# CPU.net
KiCad netlist of a schematic drawn in Altium Designer
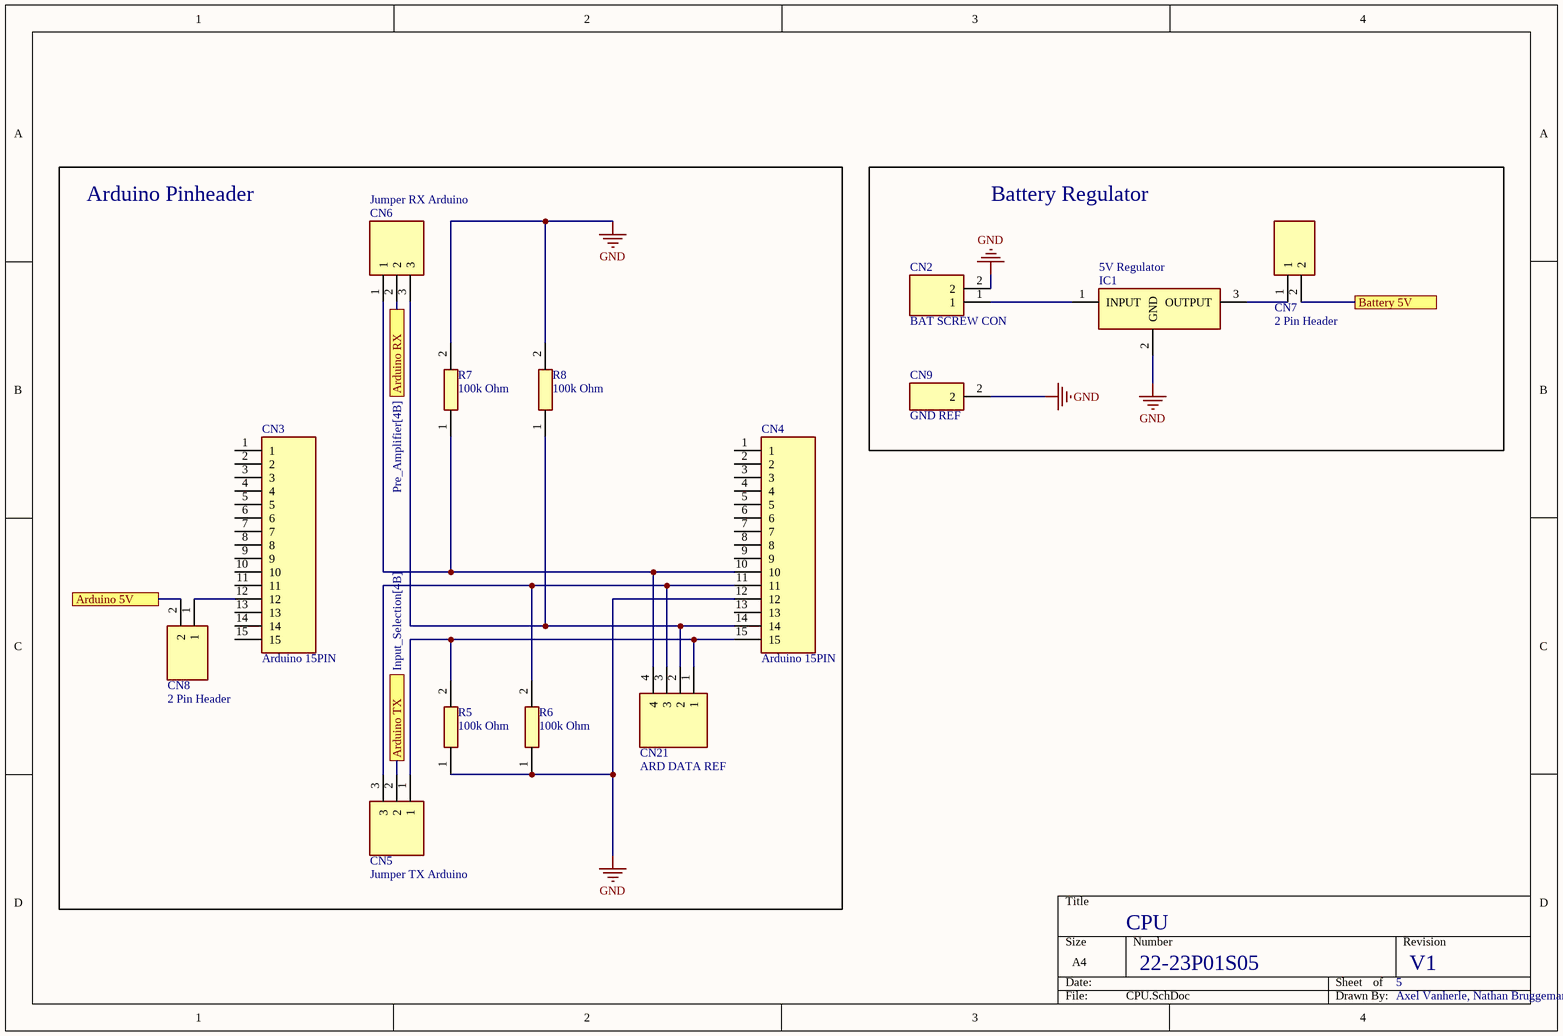
[diagram p0: CPU.SchDoc]

(export (version "E")
  (design (tool "Eeschema 10.0.6"))
  (components
    (comp (ref "CN2")
      (value "BAT SCREW CON")
      (footprint "BAT SCREW CON")
      (description "Connector")
      (fields
        (field (name "MANUFACTURER_PART_NUMBER") "TB006-508-02BE")
        (field (name "MOUSER PART NUMBER") "490-TB006-508-02BE")
      )
      (libsource (lib "IR_Communication_Schematic_Lib") (part "BAT SCREW CON"))
    )
    (comp (ref "CN3")
      (value "Arduino 15PIN")
      (footprint "15 Pin Header")
      (description "15 Pin Header Connector")
      (fields
        (field (name "MANUFACTURER_PART_NUMBER") "PRT-16279")
        (field (name "MOUSER PART NUMBER") "474-PRT-16279")
      )
      (libsource (lib "IR_Communication_Schematic_Lib") (part "15 Pin Header"))
    )
    (comp (ref "CN4")
      (value "Arduino 15PIN")
      (footprint "15 Pin Header")
      (description "15 Pin Header Connector")
      (fields
        (field (name "MANUFACTURER_PART_NUMBER") "PRT-16279")
        (field (name "MOUSER PART NUMBER") "474-PRT-16279")
      )
      (libsource (lib "IR_Communication_Schematic_Lib") (part "15 Pin Header"))
    )
    (comp (ref "CN5")
      (value "Jumper TX Arduino")
      (footprint "3 Pin Header")
      (description "TSW-103-07-G-S")
      (fields (field (name "MOUSER PART NUMBER") "200-TSW10307GS"))
      (libsource (lib "IR_Communication_Schematic_Lib") (part "3 Pin Header"))
    )
    (comp (ref "CN6")
      (value "Jumper RX Arduino")
      (footprint "3 Pin Header")
      (description "TSW-103-07-G-S")
      (fields (field (name "MOUSER PART NUMBER") "200-TSW10307GS"))
      (libsource (lib "") (part "3 Pin Header_1"))
    )
    (comp (ref "CN7")
      (value "2 Pin Header")
      (footprint "2 Pin Header")
      (description "Connector")
      (fields
        (field (name "MANUFACTURER_PART_NUMBER") "5-146284-2")
        (field (name "MOUSER PART NUMBER") "571-5-146284-2")
      )
      (libsource (lib "IR_Communication_Schematic_Lib") (part "2 Pin Header"))
    )
    (comp (ref "CN8")
      (value "2 Pin Header")
      (footprint "2 Pin Header")
      (description "Connector")
      (fields
        (field (name "MANUFACTURER_PART_NUMBER") "5-146284-2")
        (field (name "MOUSER PART NUMBER") "571-5-146284-2")
      )
      (libsource (lib "") (part "2 Pin Header_1"))
    )
    (comp (ref "CN9")
      (value "GND REF")
      (footprint "1 PIN HEADER")
      (description "Connector")
      (fields
        (field (name "MANUFACTURER_PART_NUMBER") "5-146281-1")
        (field (name "MOUSER PART NUMBER") "571-5-146281-1")
      )
      (libsource (lib "IR_Communication_Schematic_Lib") (part "1 Pin Header"))
    )
    (comp (ref "CN21")
      (value "ARD DATA REF")
      (footprint "4 PIN HEADER")
      (description "G800LW304032EU")
      (fields (field (name "MOUSER PART NUMBER") "523-G800LW304032EU"))
      (libsource (lib "IR_Communication_Schematic_Lib") (part "4 Pin Header"))
    )
    (comp (ref "IC1")
      (value "5V Regulator")
      (footprint "5V Regulator")
      (description "MC7805BDTG")
      (fields (field (name "MOUSER PART NUMBER") "863-MC7805BDTG"))
      (libsource (lib "IR_Communication_Schematic_Lib") (part "5V Regulator"))
    )
    (comp (ref "R5")
      (value "100k Ohm")
      (footprint "0805")
      (description "Resistor")
      (fields
        (field (name "MANUFACTURER_PART_NUMBER") "RP0805BRD071KL")
        (field (name "MOUSER PART NUMBER") "603-RP0805BRD071KL")
      )
      (libsource (lib "IR_Communication_Schematic_Lib") (part "Resistor"))
    )
    (comp (ref "R6")
      (value "100k Ohm")
      (footprint "0805")
      (description "Resistor")
      (fields
        (field (name "MANUFACTURER_PART_NUMBER") "RP0805BRD071KL")
        (field (name "MOUSER PART NUMBER") "603-RP0805BRD071KL")
      )
      (libsource (lib "IR_Communication_Schematic_Lib") (part "Resistor"))
    )
    (comp (ref "R7")
      (value "100k Ohm")
      (footprint "0805")
      (description "Resistor")
      (fields
        (field (name "MANUFACTURER_PART_NUMBER") "RP0805BRD071KL")
        (field (name "MOUSER PART NUMBER") "603-RP0805BRD071KL")
      )
      (libsource (lib "IR_Communication_Schematic_Lib") (part "Resistor"))
    )
    (comp (ref "R8")
      (value "100k Ohm")
      (footprint "0805")
      (description "Resistor")
      (fields
        (field (name "MANUFACTURER_PART_NUMBER") "RP0805BRD071KL")
        (field (name "MOUSER PART NUMBER") "603-RP0805BRD071KL")
      )
      (libsource (lib "IR_Communication_Schematic_Lib") (part "Resistor"))
    )
  )
  (nets
    (net (code "1") (name "/Arduino 5V") (class "Default")
      (node (ref "CN8") (pin "2") (pinfunction "2_2") (pintype "passive"))
    )
    (net (code "2") (name "/Arduino RX") (class "Default")
      (node (ref "CN6") (pin "2") (pinfunction "2_2") (pintype "passive"))
    )
    (net (code "3") (name "/Arduino TX") (class "Default")
      (node (ref "CN5") (pin "2") (pinfunction "2_2") (pintype "passive"))
    )
    (net (code "4") (name "/Battery 5V") (class "Default")
      (node (ref "CN7") (pin "2") (pinfunction "2_2") (pintype "passive"))
    )
    (net (code "5") (name "GND") (class "Default")
      (node (ref "CN2") (pin "2") (pinfunction "2_2") (pintype "passive"))
      (node (ref "CN4") (pin "12") (pinfunction "12_12") (pintype "passive"))
      (node (ref "CN9") (pin "2") (pinfunction "2_2") (pintype "passive"))
      (node (ref "IC1") (pin "2") (pinfunction "GND_2") (pintype "passive"))
      (node (ref "R5") (pin "1") (pinfunction "1_1") (pintype "passive"))
      (node (ref "R6") (pin "1") (pinfunction "1_1") (pintype "passive"))
      (node (ref "R7") (pin "2") (pinfunction "2_2") (pintype "passive"))
      (node (ref "R8") (pin "2") (pinfunction "2_2") (pintype "passive"))
    )
    (net (code "6") (name "Net-(CN3-Pad12)") (class "Default")
      (node (ref "CN3") (pin "12") (pinfunction "12_12") (pintype "passive"))
      (node (ref "CN8") (pin "1") (pinfunction "1_1") (pintype "passive"))
    )
    (net (code "7") (name "Net-(CN21-Pad1)") (class "Default")
      (node (ref "CN21") (pin "1") (pinfunction "1_1") (pintype "passive"))
      (node (ref "CN4") (pin "15") (pinfunction "15_15") (pintype "passive"))
      (node (ref "CN5") (pin "1") (pinfunction "1_1") (pintype "passive"))
      (node (ref "R5") (pin "2") (pinfunction "2_2") (pintype "passive"))
    )
    (net (code "8") (name "Net-(CN21-Pad2)") (class "Default")
      (node (ref "CN21") (pin "2") (pinfunction "2_2") (pintype "passive"))
      (node (ref "CN4") (pin "14") (pinfunction "14_14") (pintype "passive"))
      (node (ref "CN6") (pin "3") (pinfunction "3_3") (pintype "passive"))
      (node (ref "R8") (pin "1") (pinfunction "1_1") (pintype "passive"))
    )
    (net (code "9") (name "Net-(CN21-Pad3)") (class "Default")
      (node (ref "CN21") (pin "3") (pinfunction "3_3") (pintype "passive"))
      (node (ref "CN4") (pin "11") (pinfunction "11_11") (pintype "passive"))
      (node (ref "CN5") (pin "3") (pinfunction "3_3") (pintype "passive"))
      (node (ref "R6") (pin "2") (pinfunction "2_2") (pintype "passive"))
    )
    (net (code "10") (name "Net-(CN21-Pad4)") (class "Default")
      (node (ref "CN21") (pin "4") (pinfunction "4_4") (pintype "passive"))
      (node (ref "CN4") (pin "10") (pinfunction "10_10") (pintype "passive"))
      (node (ref "CN6") (pin "1") (pinfunction "1_1") (pintype "passive"))
      (node (ref "R7") (pin "1") (pinfunction "1_1") (pintype "passive"))
    )
    (net (code "11") (name "Net-(IC1-INPUT)") (class "Default")
      (node (ref "CN2") (pin "1") (pinfunction "1_1") (pintype "passive"))
      (node (ref "IC1") (pin "1") (pinfunction "INPUT_1") (pintype "passive"))
    )
    (net (code "12") (name "Net-(IC1-OUTPUT)") (class "Default")
      (node (ref "CN7") (pin "1") (pinfunction "1_1") (pintype "passive"))
      (node (ref "IC1") (pin "3") (pinfunction "OUTPUT_3") (pintype "passive"))
    )
    (net (code "13") (name "unconnected-(CN3-Pad1)") (class "Default")
      (node (ref "CN3") (pin "1") (pinfunction "1_1") (pintype "passive"))
    )
    (net (code "14") (name "unconnected-(CN3-Pad2)") (class "Default")
      (node (ref "CN3") (pin "2") (pinfunction "2_2") (pintype "passive"))
    )
    (net (code "15") (name "unconnected-(CN3-Pad3)") (class "Default")
      (node (ref "CN3") (pin "3") (pinfunction "3_3") (pintype "passive"))
    )
    (net (code "16") (name "unconnected-(CN3-Pad4)") (class "Default")
      (node (ref "CN3") (pin "4") (pinfunction "4_4") (pintype "passive"))
    )
    (net (code "17") (name "unconnected-(CN3-Pad5)") (class "Default")
      (node (ref "CN3") (pin "5") (pinfunction "5_5") (pintype "passive"))
    )
    (net (code "18") (name "unconnected-(CN3-Pad6)") (class "Default")
      (node (ref "CN3") (pin "6") (pinfunction "6_6") (pintype "passive"))
    )
    (net (code "19") (name "unconnected-(CN3-Pad7)") (class "Default")
      (node (ref "CN3") (pin "7") (pinfunction "7_7") (pintype "passive"))
    )
    (net (code "20") (name "unconnected-(CN3-Pad8)") (class "Default")
      (node (ref "CN3") (pin "8") (pinfunction "8_8") (pintype "passive"))
    )
    (net (code "21") (name "unconnected-(CN3-Pad9)") (class "Default")
      (node (ref "CN3") (pin "9") (pinfunction "9_9") (pintype "passive"))
    )
    (net (code "22") (name "unconnected-(CN3-Pad10)") (class "Default")
      (node (ref "CN3") (pin "10") (pinfunction "10_10") (pintype "passive"))
    )
    (net (code "23") (name "unconnected-(CN3-Pad11)") (class "Default")
      (node (ref "CN3") (pin "11") (pinfunction "11_11") (pintype "passive"))
    )
    (net (code "24") (name "unconnected-(CN3-Pad13)") (class "Default")
      (node (ref "CN3") (pin "13") (pinfunction "13_13") (pintype "passive"))
    )
    (net (code "25") (name "unconnected-(CN3-Pad14)") (class "Default")
      (node (ref "CN3") (pin "14") (pinfunction "14_14") (pintype "passive"))
    )
    (net (code "26") (name "unconnected-(CN3-Pad15)") (class "Default")
      (node (ref "CN3") (pin "15") (pinfunction "15_15") (pintype "passive"))
    )
    (net (code "27") (name "unconnected-(CN4-Pad1)") (class "Default")
      (node (ref "CN4") (pin "1") (pinfunction "1_1") (pintype "passive"))
    )
    (net (code "28") (name "unconnected-(CN4-Pad2)") (class "Default")
      (node (ref "CN4") (pin "2") (pinfunction "2_2") (pintype "passive"))
    )
    (net (code "29") (name "unconnected-(CN4-Pad3)") (class "Default")
      (node (ref "CN4") (pin "3") (pinfunction "3_3") (pintype "passive"))
    )
    (net (code "30") (name "unconnected-(CN4-Pad4)") (class "Default")
      (node (ref "CN4") (pin "4") (pinfunction "4_4") (pintype "passive"))
    )
    (net (code "31") (name "unconnected-(CN4-Pad5)") (class "Default")
      (node (ref "CN4") (pin "5") (pinfunction "5_5") (pintype "passive"))
    )
    (net (code "32") (name "unconnected-(CN4-Pad6)") (class "Default")
      (node (ref "CN4") (pin "6") (pinfunction "6_6") (pintype "passive"))
    )
    (net (code "33") (name "unconnected-(CN4-Pad7)") (class "Default")
      (node (ref "CN4") (pin "7") (pinfunction "7_7") (pintype "passive"))
    )
    (net (code "34") (name "unconnected-(CN4-Pad8)") (class "Default")
      (node (ref "CN4") (pin "8") (pinfunction "8_8") (pintype "passive"))
    )
    (net (code "35") (name "unconnected-(CN4-Pad9)") (class "Default")
      (node (ref "CN4") (pin "9") (pinfunction "9_9") (pintype "passive"))
    )
    (net (code "36") (name "unconnected-(CN4-Pad13)") (class "Default")
      (node (ref "CN4") (pin "13") (pinfunction "13_13") (pintype "passive"))
    )
  )
)
